# DAC_TLV5636.net
KiCad netlist of a schematic drawn in EAGLE
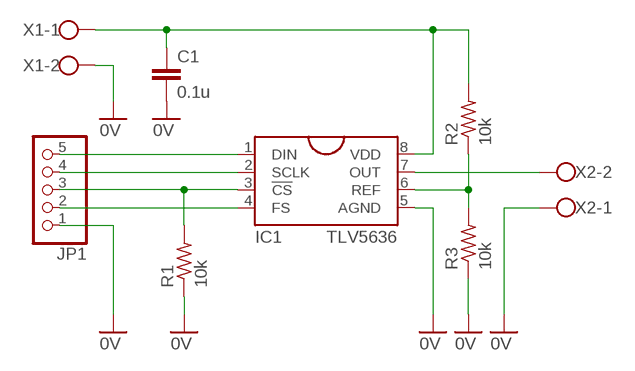
[diagram p0: schematic, sheet 1]

(export (version "E")
  (design (tool "Eeschema 10.0.6"))
  (components
    (comp (ref "C1")
      (value "0.1u")
      (footprint "eagle-import:C1206")
      (libsource (lib "eagle-import") (part "C-EUC1206"))
    )
    (comp (ref "IC1")
      (value "TLV5636")
      (footprint "eagle-import:SOIC8")
      (libsource (lib "eagle-import") (part "TLV5636"))
    )
    (comp (ref "JP1")
      (value "PINHD-1X5")
      (footprint "eagle-import:1X05")
      (libsource (lib "eagle-import") (part "PINHD-1X5"))
    )
    (comp (ref "R1")
      (value "10k")
      (footprint "eagle-import:R0805")
      (libsource (lib "eagle-import") (part "R-US_R0805"))
    )
    (comp (ref "R2")
      (value "10k")
      (footprint "eagle-import:R0805")
      (libsource (lib "eagle-import") (part "R-US_R0805"))
    )
    (comp (ref "R3")
      (value "10k")
      (footprint "eagle-import:R0805")
      (libsource (lib "eagle-import") (part "R-US_R0805"))
    )
    (comp (ref "X1")
      (value "W237-102")
      (footprint "eagle-import:W237-102")
      (fields (field (name "MPN") "237-102"))
      (libsource (lib "eagle-import") (part "W237-102"))
    )
    (comp (ref "X2")
      (value "W237-102")
      (footprint "eagle-import:W237-102")
      (fields (field (name "MPN") "237-102"))
      (libsource (lib "eagle-import") (part "W237-102"))
    )
  )
  (nets
    (net (code "1") (name "0V") (class "Default")
      (node (ref "C1") (pin "2") (pinfunction "2_2") (pintype "passive"))
      (node (ref "IC1") (pin "5") (pinfunction "AGND_5") (pintype "bidirectional"))
      (node (ref "JP1") (pin "1") (pinfunction "1_1") (pintype "passive"))
      (node (ref "R1") (pin "1") (pinfunction "1_1") (pintype "passive"))
      (node (ref "R3") (pin "1") (pinfunction "1_1") (pintype "passive"))
      (node (ref "X1") (pin "2") (pinfunction "KL_2") (pintype "passive"))
      (node (ref "X2") (pin "1") (pinfunction "KL_1") (pintype "passive"))
    )
    (net (code "2") (name "Net-(IC1-DIN)") (class "Default")
      (node (ref "IC1") (pin "1") (pinfunction "DIN_1") (pintype "bidirectional"))
      (node (ref "JP1") (pin "5") (pinfunction "5_5") (pintype "passive"))
    )
    (net (code "3") (name "Net-(IC1-FS)") (class "Default")
      (node (ref "IC1") (pin "4") (pinfunction "FS_4") (pintype "bidirectional"))
      (node (ref "JP1") (pin "2") (pinfunction "2_2") (pintype "passive"))
    )
    (net (code "4") (name "Net-(IC1-OUT)") (class "Default")
      (node (ref "IC1") (pin "7") (pinfunction "OUT_7") (pintype "bidirectional"))
      (node (ref "X2") (pin "2") (pinfunction "KL_2") (pintype "passive"))
    )
    (net (code "5") (name "Net-(IC1-REF)") (class "Default")
      (node (ref "IC1") (pin "6") (pinfunction "REF_6") (pintype "bidirectional"))
      (node (ref "R2") (pin "1") (pinfunction "1_1") (pintype "passive"))
      (node (ref "R3") (pin "2") (pinfunction "2_2") (pintype "passive"))
    )
    (net (code "6") (name "Net-(IC1-SCLK)") (class "Default")
      (node (ref "IC1") (pin "2") (pinfunction "SCLK_2") (pintype "bidirectional"))
      (node (ref "JP1") (pin "4") (pinfunction "4_4") (pintype "passive"))
    )
    (net (code "7") (name "Net-(IC1-VDD)") (class "Default")
      (node (ref "C1") (pin "1") (pinfunction "1_1") (pintype "passive"))
      (node (ref "IC1") (pin "8") (pinfunction "VDD_8") (pintype "bidirectional"))
      (node (ref "R2") (pin "2") (pinfunction "2_2") (pintype "passive"))
      (node (ref "X1") (pin "1") (pinfunction "KL_1") (pintype "passive"))
    )
    (net (code "8") (name "Net-(IC1-~{CS})") (class "Default")
      (node (ref "IC1") (pin "3") (pinfunction "~{CS}_3") (pintype "bidirectional"))
      (node (ref "JP1") (pin "3") (pinfunction "3_3") (pintype "passive"))
      (node (ref "R1") (pin "2") (pinfunction "2_2") (pintype "passive"))
    )
  )
)
